# POWER.net
KiCad netlist of a schematic drawn in Altium Designer
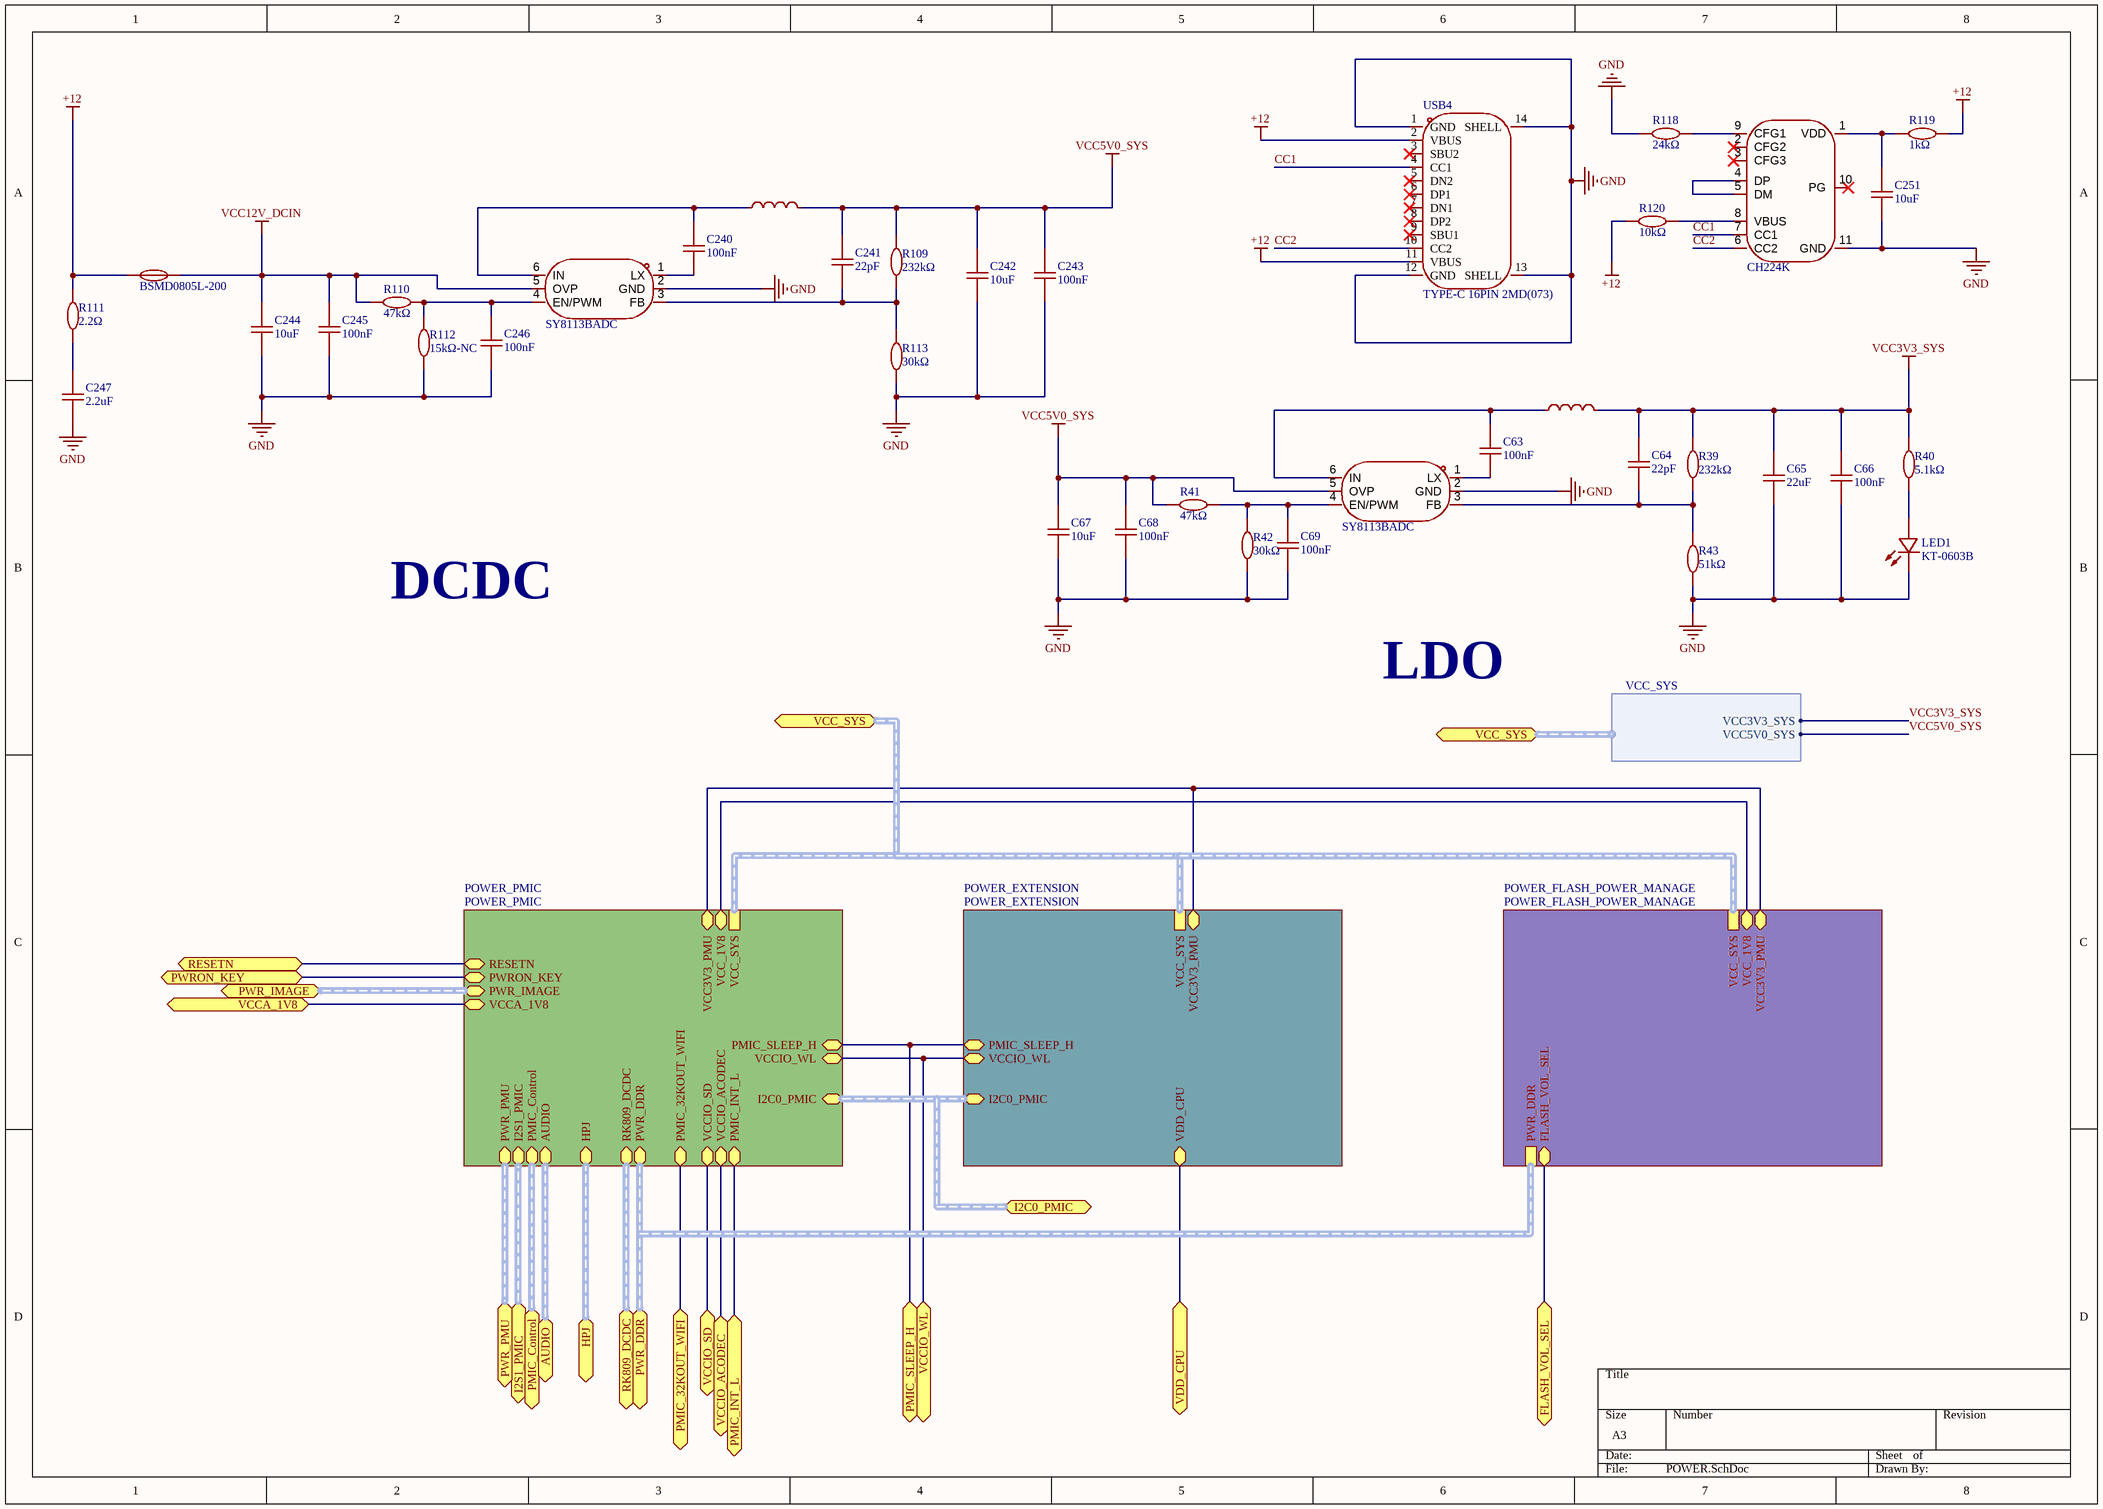
[diagram p0: POWER.SchDoc]

(export (version "E")
  (design (tool "Eeschema 10.0.6"))
  (components
    (comp (ref "C63")
      (value "100nF")
      (footprint "C0402")
      (description "50V 100nF X7R ±10% 0402 Ceramic Capacitors ROHS")
      (libsource (lib "RLC") (part "100nF"))
    )
    (comp (ref "C64")
      (value "22pF")
      (footprint "C0402")
      (description "50V 22pF C0G ±5% 0402 Ceramic Capacitors ROHS")
      (libsource (lib "RLC") (part "22pF"))
    )
    (comp (ref "C65")
      (value "22uF")
      (footprint "C0603")
      (description "16V 22uF X5R ±20% 0603 Ceramic Capacitors ROHS")
      (libsource (lib "RLC") (part "22uF"))
    )
    (comp (ref "C66")
      (value "100nF")
      (footprint "C0402")
      (description "50V 100nF X7R ±10% 0402 Ceramic Capacitors ROHS")
      (libsource (lib "RLC") (part "100nF"))
    )
    (comp (ref "C67")
      (value "10uF")
      (footprint "C0603")
      (description "10V 10uF X5R ±10% 0603 Ceramic Capacitors ROHS")
      (libsource (lib "RLC") (part "10uF"))
    )
    (comp (ref "C68")
      (value "100nF")
      (footprint "C0402")
      (description "50V 100nF X7R ±10% 0402 Ceramic Capacitors ROHS")
      (libsource (lib "RLC") (part "100nF"))
    )
    (comp (ref "C69")
      (value "100nF")
      (footprint "C0402")
      (description "50V 100nF X7R ±10% 0402 Ceramic Capacitors ROHS")
      (libsource (lib "RLC") (part "100nF"))
    )
    (comp (ref "C240")
      (value "100nF")
      (footprint "C0402")
      (description "50V 100nF X7R ±10% 0402 Ceramic Capacitors ROHS")
      (libsource (lib "RLC") (part "100nF"))
    )
    (comp (ref "C241")
      (value "22pF")
      (footprint "C0402")
      (description "50V 22pF C0G ±5% 0402 Ceramic Capacitors ROHS")
      (libsource (lib "RLC") (part "22pF"))
    )
    (comp (ref "C242")
      (value "10uF")
      (footprint "C0603")
      (description "10V 10uF X5R ±10% 0603 Ceramic Capacitors ROHS")
      (libsource (lib "RLC") (part "10uF"))
    )
    (comp (ref "C243")
      (value "100nF")
      (footprint "C0402")
      (description "50V 100nF X7R ±10% 0402 Ceramic Capacitors ROHS")
      (libsource (lib "RLC") (part "100nF"))
    )
    (comp (ref "C244")
      (value "10uF")
      (footprint "C0603")
      (description "10V 10uF X5R ±10% 0603 Ceramic Capacitors ROHS")
      (libsource (lib "RLC") (part "10uF"))
    )
    (comp (ref "C245")
      (value "100nF")
      (footprint "C0402")
      (description "50V 100nF X7R ±10% 0402 Ceramic Capacitors ROHS")
      (libsource (lib "RLC") (part "100nF"))
    )
    (comp (ref "C246")
      (value "100nF")
      (footprint "C0402")
      (description "50V 100nF X7R ±10% 0402 Ceramic Capacitors ROHS")
      (libsource (lib "RLC") (part "100nF"))
    )
    (comp (ref "C247")
      (value "2.2uF")
      (footprint "C0402")
      (description "50V 2.2uF NP0 0402 Ceramic Capacitors ROHS")
      (libsource (lib "RLC") (part "2.2uF"))
    )
    (comp (ref "C251")
      (value "10uF")
      (footprint "C0603")
      (description "10V 10uF X5R ±10% 0603 Ceramic Capacitors ROHS")
      (libsource (lib "RLC") (part "10uF"))
    )
    (comp (ref "F2")
      (value "BSMD0805L-200")
      (footprint "F0805")
      (description "6V 2A 0805自恢复")
      (libsource (lib "LED") (part "BSMD0805L-200"))
    )
    (comp (ref "L2")
      (value "3.3uH")
      (footprint "IND-SMD_L4.4-W4.2")
      (fields
        (field (name "MANUFACTURER") "Sunltech(顺磁)")
        (field (name "MANUFACTURER PART") "SLW4030S1R0NST")
        (field (name "TOLERANCE") "±30%")
      )
      (libsource (lib "RLC") (part "MWSA0402S-3R3MT"))
    )
    (comp (ref "L11")
      (value "6.8uH")
      (footprint "IND-SMD_L4.4-W4.2")
      (description "6.8uH ±20% 2.5A SMD，4.4x4.2x1.8mm   合金电感，一体成型电感，大电流")
      (fields
        (field (name "MANUFACTURER") "Sunltech(顺磁)")
        (field (name "MANUFACTURER PART") "SLW4030S1R0NST")
      )
      (libsource (lib "RLC") (part "FXL0420-6R8-M"))
    )
    (comp (ref "LED1")
      (value "KT-0603B")
      (footprint "LED0603-BL")
      (description "30mA 2.6V~3.2V Blue 0603 LED Indication - Discrete ROHS")
      (libsource (lib "LED") (part "KT-0603B"))
    )
    (comp (ref "R39")
      (value "232kΩ")
      (footprint "R0402")
      (description "62.5mW 232kΩ 50V ±100ppm/℃ Thick Film Resistor ±1% 0402 Chip Resistor - Surface Mount ROHS")
      (libsource (lib "RLC") (part "232kΩ"))
    )
    (comp (ref "R40")
      (value "5.1kΩ")
      (footprint "R0402")
      (description "5.1kΩ 62.5mW 50V ±100ppm/℃ Thick Film Resistor ±1% 0402 Chip Resistor - Surface Mount ROHS")
      (libsource (lib "RLC") (part "5.1kΩ"))
    )
    (comp (ref "R41")
      (value "47kΩ")
      (footprint "R0402")
      (description "62.5mW 47kΩ 50V ±100ppm/℃ Thick Film Resistor ±1% 0402 Chip Resistor - Surface Mount ROHS")
      (libsource (lib "RLC") (part "47kΩ"))
    )
    (comp (ref "R42")
      (value "30kΩ")
      (footprint "R0402")
      (description "62.5mW 30K 50V ±100ppm/℃ Thick Film Resistor ±1% 0402 Chip Resistor - Surface Mount ROHS")
      (libsource (lib "RLC") (part "30kΩ"))
    )
    (comp (ref "R43")
      (value "51kΩ")
      (footprint "R0402")
      (description "51kΩ 62.5mW 50V ±100ppm/℃ Thick Film Resistor ±1% 0402 Chip Resistor - Surface Mount ROHS")
      (libsource (lib "RLC") (part "51kΩ"))
    )
    (comp (ref "R109")
      (value "232kΩ")
      (footprint "R0402")
      (description "62.5mW 232kΩ 50V ±100ppm/℃ Thick Film Resistor ±1% 0402 Chip Resistor - Surface Mount ROHS")
      (libsource (lib "RLC") (part "232kΩ"))
    )
    (comp (ref "R110")
      (value "47kΩ")
      (footprint "R0402")
      (description "62.5mW 47kΩ 50V ±100ppm/℃ Thick Film Resistor ±1% 0402 Chip Resistor - Surface Mount ROHS")
      (libsource (lib "RLC") (part "47kΩ"))
    )
    (comp (ref "R111")
      (value "2.2Ω")
      (footprint "R0402")
      (description "小尺寸、重量轻。降低组装成本,与贴片机匹配。适用于波峰焊和回流焊")
      (libsource (lib "RLC") (part "2.2Ω"))
    )
    (comp (ref "R112")
      (value "15kΩ-NC")
      (footprint "R0402")
      (description "62.5mW 30K 50V ±100ppm/℃ Thick Film Resistor ±1% 0402 Chip Resistor - Surface Mount ROHS")
      (libsource (lib "RLC") (part "30kΩ"))
    )
    (comp (ref "R113")
      (value "30kΩ")
      (footprint "R0402")
      (description "62.5mW 30K 50V ±100ppm/℃ Thick Film Resistor ±1% 0402 Chip Resistor - Surface Mount ROHS")
      (libsource (lib "RLC") (part "30kΩ"))
    )
    (comp (ref "R118")
      (value "24kΩ")
      (footprint "R0402")
      (description "24kΩ 62.5mW 50V ±100ppm/℃ Thick Film Resistor ±1% 0402 Chip Resistor - Surface Mount ROHS")
      (libsource (lib "RLC") (part "24kΩ"))
    )
    (comp (ref "R119")
      (value "1kΩ")
      (footprint "R0402")
      (description "1kΩ 62.5mW 50V ±100ppm/℃ Thick Film Resistor ±1% 0402 Chip Resistor - Surface Mount ROHS")
      (libsource (lib "RLC") (part "1kΩ"))
    )
    (comp (ref "R120")
      (value "10kΩ")
      (footprint "R0402")
      (description "62.5mW 10kΩ 50V ±100ppm/℃ Thick Film Resistor ±1% 0402 Chip Resistor - Surface Mount ROHS")
      (libsource (lib "RLC") (part "10kΩ"))
    )
    (comp (ref "U19")
      (value "SY8113BADC")
      (footprint "SOT-23-6_L2.9-W1.6-P0.95-LS2.8-BR")
      (libsource (lib "IC") (part "SY8113BADC"))
    )
    (comp (ref "U22")
      (value "CH224K")
      (footprint "ESSOP-10_L4.9-W3.9-P1.0-LS6.0-TL-EP")
      (description "USBPD等多快充协议受电芯片CH224 ESSOP-10-150mil-1mm")
      (libsource (lib "IC") (part "CH224K"))
    )
    (comp (ref "U41")
      (value "SY8113BADC")
      (footprint "SOT-23-6_L2.9-W1.6-P0.95-LS2.8-BR")
      (libsource (lib "IC") (part "SY8113BADC"))
    )
    (comp (ref "USB4")
      (value "TYPE-C 16PIN 2MD(073)")
      (footprint "USB-C-SMD_TYPE-C-6PIN-2MD-073")
      (description "16pin type-c")
      (libsource (lib "Connector") (part "TYPE-C 16PIN 2MD(073)"))
    )
  )
  (nets
    (net (code "10") (name "+12") (class "Default")
      (node (ref "F2") (pin "1") (pinfunction "1_1") (pintype "passive"))
      (node (ref "R111") (pin "2") (pinfunction "2_2") (pintype "passive"))
      (node (ref "R119") (pin "2") (pinfunction "2_2") (pintype "passive"))
      (node (ref "R120") (pin "1") (pinfunction "1_1") (pintype "passive"))
      (node (ref "USB4") (pin "11") (pinfunction "VBUS_11") (pintype "passive"))
      (node (ref "USB4") (pin "2") (pinfunction "VBUS_2") (pintype "passive"))
    )
    (net (code "12") (name "/CC1") (class "Default")
      (node (ref "U22") (pin "7") (pinfunction "CC1_7") (pintype "passive"))
      (node (ref "USB4") (pin "4") (pinfunction "CC1_4") (pintype "passive"))
    )
    (net (code "13") (name "/CC2") (class "Default")
      (node (ref "U22") (pin "6") (pinfunction "CC2_6") (pintype "passive"))
      (node (ref "USB4") (pin "10") (pinfunction "CC2_10") (pintype "passive"))
    )
    (net (code "36") (name "GND") (class "Default")
      (node (ref "C242") (pin "1") (pinfunction "1_1") (pintype "passive"))
      (node (ref "C243") (pin "1") (pinfunction "1_1") (pintype "passive"))
      (node (ref "C244") (pin "1") (pinfunction "1_1") (pintype "passive"))
      (node (ref "C245") (pin "1") (pinfunction "1_1") (pintype "passive"))
      (node (ref "C246") (pin "1") (pinfunction "1_1") (pintype "passive"))
      (node (ref "C247") (pin "1") (pinfunction "1_1") (pintype "passive"))
      (node (ref "C251") (pin "1") (pinfunction "1_1") (pintype "passive"))
      (node (ref "C65") (pin "1") (pinfunction "1_1") (pintype "passive"))
      (node (ref "C66") (pin "1") (pinfunction "1_1") (pintype "passive"))
      (node (ref "C67") (pin "1") (pinfunction "1_1") (pintype "passive"))
      (node (ref "C68") (pin "1") (pinfunction "1_1") (pintype "passive"))
      (node (ref "C69") (pin "1") (pinfunction "1_1") (pintype "passive"))
      (node (ref "LED1") (pin "1") (pinfunction "K_1") (pintype "passive"))
      (node (ref "R112") (pin "1") (pinfunction "1_1") (pintype "passive"))
      (node (ref "R113") (pin "1") (pinfunction "1_1") (pintype "passive"))
      (node (ref "R118") (pin "1") (pinfunction "1_1") (pintype "passive"))
      (node (ref "R42") (pin "1") (pinfunction "1_1") (pintype "passive"))
      (node (ref "R43") (pin "1") (pinfunction "1_1") (pintype "passive"))
      (node (ref "U19") (pin "2") (pinfunction "GND_2") (pintype "passive"))
      (node (ref "U22") (pin "11") (pinfunction "GND_11") (pintype "passive"))
      (node (ref "U41") (pin "2") (pinfunction "GND_2") (pintype "passive"))
      (node (ref "USB4") (pin "1") (pinfunction "GND_1") (pintype "passive"))
      (node (ref "USB4") (pin "12") (pinfunction "GND_12") (pintype "passive"))
      (node (ref "USB4") (pin "13") (pinfunction "SHELL_13") (pintype "passive"))
      (node (ref "USB4") (pin "14") (pinfunction "SHELL_14") (pintype "passive"))
    )
    (net (code "37") (name "Net-(C247-Pad2)") (class "Default")
      (node (ref "C247") (pin "2") (pinfunction "2_2") (pintype "passive"))
      (node (ref "R111") (pin "1") (pinfunction "1_1") (pintype "passive"))
    )
    (net (code "38") (name "Net-(LED1-A)") (class "Default")
      (node (ref "LED1") (pin "2") (pinfunction "A_2") (pintype "passive"))
      (node (ref "R40") (pin "1") (pinfunction "1_1") (pintype "passive"))
    )
    (net (code "39") (name "Net-(U19-EN{slash}PWM)") (class "Default")
      (node (ref "C69") (pin "2") (pinfunction "2_2") (pintype "passive"))
      (node (ref "R41") (pin "2") (pinfunction "2_2") (pintype "passive"))
      (node (ref "R42") (pin "2") (pinfunction "2_2") (pintype "passive"))
      (node (ref "U19") (pin "4") (pinfunction "EN/PWM_4") (pintype "passive"))
    )
    (net (code "40") (name "Net-(U19-FB)") (class "Default")
      (node (ref "C64") (pin "1") (pinfunction "1_1") (pintype "passive"))
      (node (ref "R39") (pin "1") (pinfunction "1_1") (pintype "passive"))
      (node (ref "R43") (pin "2") (pinfunction "2_2") (pintype "passive"))
      (node (ref "U19") (pin "3") (pinfunction "FB_3") (pintype "passive"))
    )
    (net (code "41") (name "Net-(U19-IN)") (class "Default")
      (node (ref "C63") (pin "2") (pinfunction "2_2") (pintype "passive"))
      (node (ref "L2") (pin "1") (pinfunction "1_1") (pintype "passive"))
      (node (ref "U19") (pin "6") (pinfunction "IN_6") (pintype "passive"))
    )
    (net (code "42") (name "Net-(U19-LX)") (class "Default")
      (node (ref "C63") (pin "1") (pinfunction "1_1") (pintype "passive"))
      (node (ref "U19") (pin "1") (pinfunction "LX_1") (pintype "passive"))
    )
    (net (code "43") (name "Net-(U22-CFG1)") (class "Default")
      (node (ref "R118") (pin "2") (pinfunction "2_2") (pintype "passive"))
      (node (ref "U22") (pin "9") (pinfunction "CFG1_9") (pintype "passive"))
    )
    (net (code "44") (name "Net-(U22-DM)") (class "Default")
      (node (ref "U22") (pin "4") (pinfunction "DP_4") (pintype "passive"))
      (node (ref "U22") (pin "5") (pinfunction "DM_5") (pintype "passive"))
    )
    (net (code "45") (name "Net-(U22-VBUS)") (class "Default")
      (node (ref "R120") (pin "2") (pinfunction "2_2") (pintype "passive"))
      (node (ref "U22") (pin "8") (pinfunction "VBUS_8") (pintype "passive"))
    )
    (net (code "46") (name "Net-(U22-VDD)") (class "Default")
      (node (ref "C251") (pin "2") (pinfunction "2_2") (pintype "passive"))
      (node (ref "R119") (pin "1") (pinfunction "1_1") (pintype "passive"))
      (node (ref "U22") (pin "1") (pinfunction "VDD_1") (pintype "passive"))
    )
    (net (code "47") (name "Net-(U41-EN{slash}PWM)") (class "Default")
      (node (ref "C246") (pin "2") (pinfunction "2_2") (pintype "passive"))
      (node (ref "R110") (pin "2") (pinfunction "2_2") (pintype "passive"))
      (node (ref "R112") (pin "2") (pinfunction "2_2") (pintype "passive"))
      (node (ref "U41") (pin "4") (pinfunction "EN/PWM_4") (pintype "passive"))
    )
    (net (code "48") (name "Net-(U41-FB)") (class "Default")
      (node (ref "C241") (pin "1") (pinfunction "1_1") (pintype "passive"))
      (node (ref "R109") (pin "1") (pinfunction "1_1") (pintype "passive"))
      (node (ref "R113") (pin "2") (pinfunction "2_2") (pintype "passive"))
      (node (ref "U41") (pin "3") (pinfunction "FB_3") (pintype "passive"))
    )
    (net (code "49") (name "Net-(U41-IN)") (class "Default")
      (node (ref "C240") (pin "2") (pinfunction "2_2") (pintype "passive"))
      (node (ref "L11") (pin "1") (pinfunction "1_1") (pintype "passive"))
      (node (ref "U41") (pin "6") (pinfunction "IN_6") (pintype "passive"))
    )
    (net (code "50") (name "Net-(U41-LX)") (class "Default")
      (node (ref "C240") (pin "1") (pinfunction "1_1") (pintype "passive"))
      (node (ref "U41") (pin "1") (pinfunction "LX_1") (pintype "passive"))
    )
    (net (code "51") (name "VCC3V3_SYS") (class "Default")
      (node (ref "C64") (pin "2") (pinfunction "2_2") (pintype "passive"))
      (node (ref "C65") (pin "2") (pinfunction "2_2") (pintype "passive"))
      (node (ref "C66") (pin "2") (pinfunction "2_2") (pintype "passive"))
      (node (ref "L2") (pin "2") (pinfunction "2_2") (pintype "passive"))
      (node (ref "R39") (pin "2") (pinfunction "2_2") (pintype "passive"))
      (node (ref "R40") (pin "2") (pinfunction "2_2") (pintype "passive"))
    )
    (net (code "52") (name "VCC5V0_SYS") (class "Default")
      (node (ref "C241") (pin "2") (pinfunction "2_2") (pintype "passive"))
      (node (ref "C242") (pin "2") (pinfunction "2_2") (pintype "passive"))
      (node (ref "C243") (pin "2") (pinfunction "2_2") (pintype "passive"))
      (node (ref "C67") (pin "2") (pinfunction "2_2") (pintype "passive"))
      (node (ref "C68") (pin "2") (pinfunction "2_2") (pintype "passive"))
      (node (ref "L11") (pin "2") (pinfunction "2_2") (pintype "passive"))
      (node (ref "R109") (pin "2") (pinfunction "2_2") (pintype "passive"))
      (node (ref "R41") (pin "1") (pinfunction "1_1") (pintype "passive"))
      (node (ref "U19") (pin "5") (pinfunction "OVP_5") (pintype "passive"))
    )
    (net (code "53") (name "VCC12V_DCIN") (class "Default")
      (node (ref "C244") (pin "2") (pinfunction "2_2") (pintype "passive"))
      (node (ref "C245") (pin "2") (pinfunction "2_2") (pintype "passive"))
      (node (ref "F2") (pin "2") (pinfunction "2_2") (pintype "passive"))
      (node (ref "R110") (pin "1") (pinfunction "1_1") (pintype "passive"))
      (node (ref "U41") (pin "5") (pinfunction "OVP_5") (pintype "passive"))
    )
    (net (code "54") (name "unconnected-(U22-CFG2-Pad2)") (class "Default")
      (node (ref "U22") (pin "2") (pinfunction "CFG2_2") (pintype "passive+no_connect"))
    )
    (net (code "55") (name "unconnected-(U22-CFG3-Pad3)") (class "Default")
      (node (ref "U22") (pin "3") (pinfunction "CFG3_3") (pintype "passive+no_connect"))
    )
    (net (code "56") (name "unconnected-(U22-PG-Pad10)") (class "Default")
      (node (ref "U22") (pin "10") (pinfunction "PG_10") (pintype "passive+no_connect"))
    )
    (net (code "57") (name "unconnected-(USB4-DN1-Pad7)") (class "Default")
      (node (ref "USB4") (pin "7") (pinfunction "DN1_7") (pintype "passive+no_connect"))
    )
    (net (code "58") (name "unconnected-(USB4-DN2-Pad5)") (class "Default")
      (node (ref "USB4") (pin "5") (pinfunction "DN2_5") (pintype "passive+no_connect"))
    )
    (net (code "59") (name "unconnected-(USB4-DP1-Pad6)") (class "Default")
      (node (ref "USB4") (pin "6") (pinfunction "DP1_6") (pintype "passive+no_connect"))
    )
    (net (code "60") (name "unconnected-(USB4-DP2-Pad8)") (class "Default")
      (node (ref "USB4") (pin "8") (pinfunction "DP2_8") (pintype "passive+no_connect"))
    )
    (net (code "61") (name "unconnected-(USB4-SBU1-Pad9)") (class "Default")
      (node (ref "USB4") (pin "9") (pinfunction "SBU1_9") (pintype "passive+no_connect"))
    )
    (net (code "62") (name "unconnected-(USB4-SBU2-Pad3)") (class "Default")
      (node (ref "USB4") (pin "3") (pinfunction "SBU2_3") (pintype "passive+no_connect"))
    )
  )
)
